# LED-Treiber1.net
KiCad netlist of a schematic drawn in EAGLE
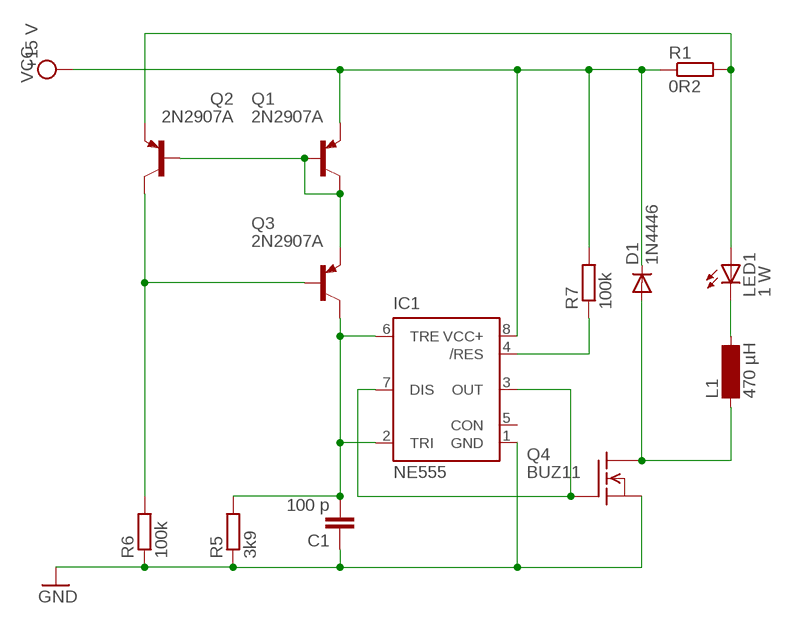
[diagram p0: schematic, sheet 1]

(export (version "E")
  (design (tool "Eeschema 10.0.6"))
  (components
    (comp (ref "C1")
      (value "100 p")
      (footprint "eagle-import:C2.5-3")
      (libsource (lib "eagle-import") (part "C2,5-3"))
    )
    (comp (ref "D1")
      (value "1N4446")
      (footprint "eagle-import:DO35-10")
      (libsource (lib "eagle-import") (part "1N4446"))
    )
    (comp (ref "IC1")
      (value "NE555")
      (footprint "eagle-import:DIL-08")
      (fields (field (name "MF") "Arrow Electronics") (field (name "MPN") "NE555N"))
      (libsource (lib "eagle-import") (part "NE555"))
    )
    (comp (ref "L1")
      (value "470 µH")
      (footprint "eagle-import:MS85")
      (libsource (lib "eagle-import") (part "MS85"))
    )
    (comp (ref "LED1")
      (value "1 W")
      (footprint "eagle-import:LED5MM")
      (libsource (lib "eagle-import") (part "LED5MM"))
    )
    (comp (ref "Q1")
      (value "2N2907A")
      (footprint "eagle-import:TO18")
      (libsource (lib "eagle-import") (part "2N2907A"))
    )
    (comp (ref "Q2")
      (value "2N2907A")
      (footprint "eagle-import:TO18")
      (libsource (lib "eagle-import") (part "2N2907A"))
    )
    (comp (ref "Q3")
      (value "2N2907A")
      (footprint "eagle-import:TO18")
      (libsource (lib "eagle-import") (part "2N2907A"))
    )
    (comp (ref "Q4")
      (value "BUZ11")
      (footprint "eagle-import:TO220")
      (libsource (lib "eagle-import") (part "BUZ11"))
    )
    (comp (ref "R1")
      (value "0R2")
      (footprint "eagle-import:0207_10")
      (libsource (lib "eagle-import") (part "R-EU_0207/10"))
    )
    (comp (ref "R5")
      (value "3k9")
      (footprint "eagle-import:0207_10")
      (libsource (lib "eagle-import") (part "R-EU_0207/10"))
    )
    (comp (ref "R6")
      (value "100k")
      (footprint "eagle-import:0207_10")
      (libsource (lib "eagle-import") (part "R-EU_0207/10"))
    )
    (comp (ref "R7")
      (value "100k")
      (footprint "eagle-import:0207_10")
      (libsource (lib "eagle-import") (part "R-EU_0207/10"))
    )
  )
  (nets
    (net (code "1") (name "GND") (class "Default")
      (node (ref "C1") (pin "1") (pinfunction "1_1") (pintype "passive"))
      (node (ref "IC1") (pin "1") (pinfunction "GND_1") (pintype "power_in"))
      (node (ref "Q4") (pin "3") (pinfunction "S_3") (pintype "passive"))
      (node (ref "R5") (pin "1") (pinfunction "1_1") (pintype "passive"))
      (node (ref "R6") (pin "1") (pinfunction "1_1") (pintype "passive"))
    )
    (net (code "2") (name "Net-(IC1-DIS)") (class "Default")
      (node (ref "IC1") (pin "3") (pinfunction "OUT_3") (pintype "output"))
      (node (ref "IC1") (pin "7") (pinfunction "DIS_7") (pintype "input"))
      (node (ref "Q4") (pin "1") (pinfunction "G_1") (pintype "passive"))
    )
    (net (code "3") (name "Net-(IC1-TRE)") (class "Default")
      (node (ref "C1") (pin "2") (pinfunction "2_2") (pintype "passive"))
      (node (ref "IC1") (pin "2") (pinfunction "TRI_2") (pintype "input"))
      (node (ref "IC1") (pin "6") (pinfunction "TRE_6") (pintype "input"))
      (node (ref "Q3") (pin "3") (pinfunction "C_3") (pintype "passive"))
      (node (ref "R5") (pin "2") (pinfunction "2_2") (pintype "passive"))
    )
    (net (code "4") (name "Net-(IC1-{slash}RES)") (class "Default")
      (node (ref "IC1") (pin "4") (pinfunction "/RES_4") (pintype "input"))
      (node (ref "R7") (pin "1") (pinfunction "1_1") (pintype "passive"))
    )
    (net (code "5") (name "Net-(LED1-C)") (class "Default")
      (node (ref "L1") (pin "2") (pinfunction "2_2") (pintype "passive"))
      (node (ref "LED1") (pin "K") (pinfunction "C_K") (pintype "passive"))
    )
    (net (code "6") (name "Net-(Q1-B)") (class "Default")
      (node (ref "Q1") (pin "2") (pinfunction "B_2") (pintype "passive"))
      (node (ref "Q1") (pin "3") (pinfunction "C_3") (pintype "passive"))
      (node (ref "Q2") (pin "2") (pinfunction "B_2") (pintype "passive"))
      (node (ref "Q3") (pin "1") (pinfunction "E_1") (pintype "passive"))
    )
    (net (code "7") (name "Net-(Q2-C)") (class "Default")
      (node (ref "Q2") (pin "3") (pinfunction "C_3") (pintype "passive"))
      (node (ref "Q3") (pin "2") (pinfunction "B_2") (pintype "passive"))
      (node (ref "R6") (pin "2") (pinfunction "2_2") (pintype "passive"))
    )
    (net (code "8") (name "Net-(Q2-E)") (class "Default")
      (node (ref "LED1") (pin "A") (pinfunction "A_A") (pintype "passive"))
      (node (ref "Q2") (pin "1") (pinfunction "E_1") (pintype "passive"))
      (node (ref "R1") (pin "2") (pinfunction "2_2") (pintype "passive"))
    )
    (net (code "9") (name "Net-(Q4-D)") (class "Default")
      (node (ref "D1") (pin "A") (pinfunction "A_A") (pintype "passive"))
      (node (ref "L1") (pin "1") (pinfunction "1_1") (pintype "passive"))
      (node (ref "Q4") (pin "2") (pinfunction "D_2") (pintype "passive"))
    )
    (net (code "10") (name "VCC") (class "Default")
      (node (ref "D1") (pin "C") (pinfunction "C_C") (pintype "passive"))
      (node (ref "IC1") (pin "8") (pinfunction "VCC+_8") (pintype "power_in"))
      (node (ref "Q1") (pin "1") (pinfunction "E_1") (pintype "passive"))
      (node (ref "R1") (pin "1") (pinfunction "1_1") (pintype "passive"))
      (node (ref "R7") (pin "2") (pinfunction "2_2") (pintype "passive"))
    )
    (net (code "11") (name "unconnected-(IC1-CON-Pad5)") (class "Default")
      (node (ref "IC1") (pin "5") (pinfunction "CON_5") (pintype "input"))
    )
  )
)
